# Capteur.net
KiCad netlist of a schematic drawn in Altium Designer
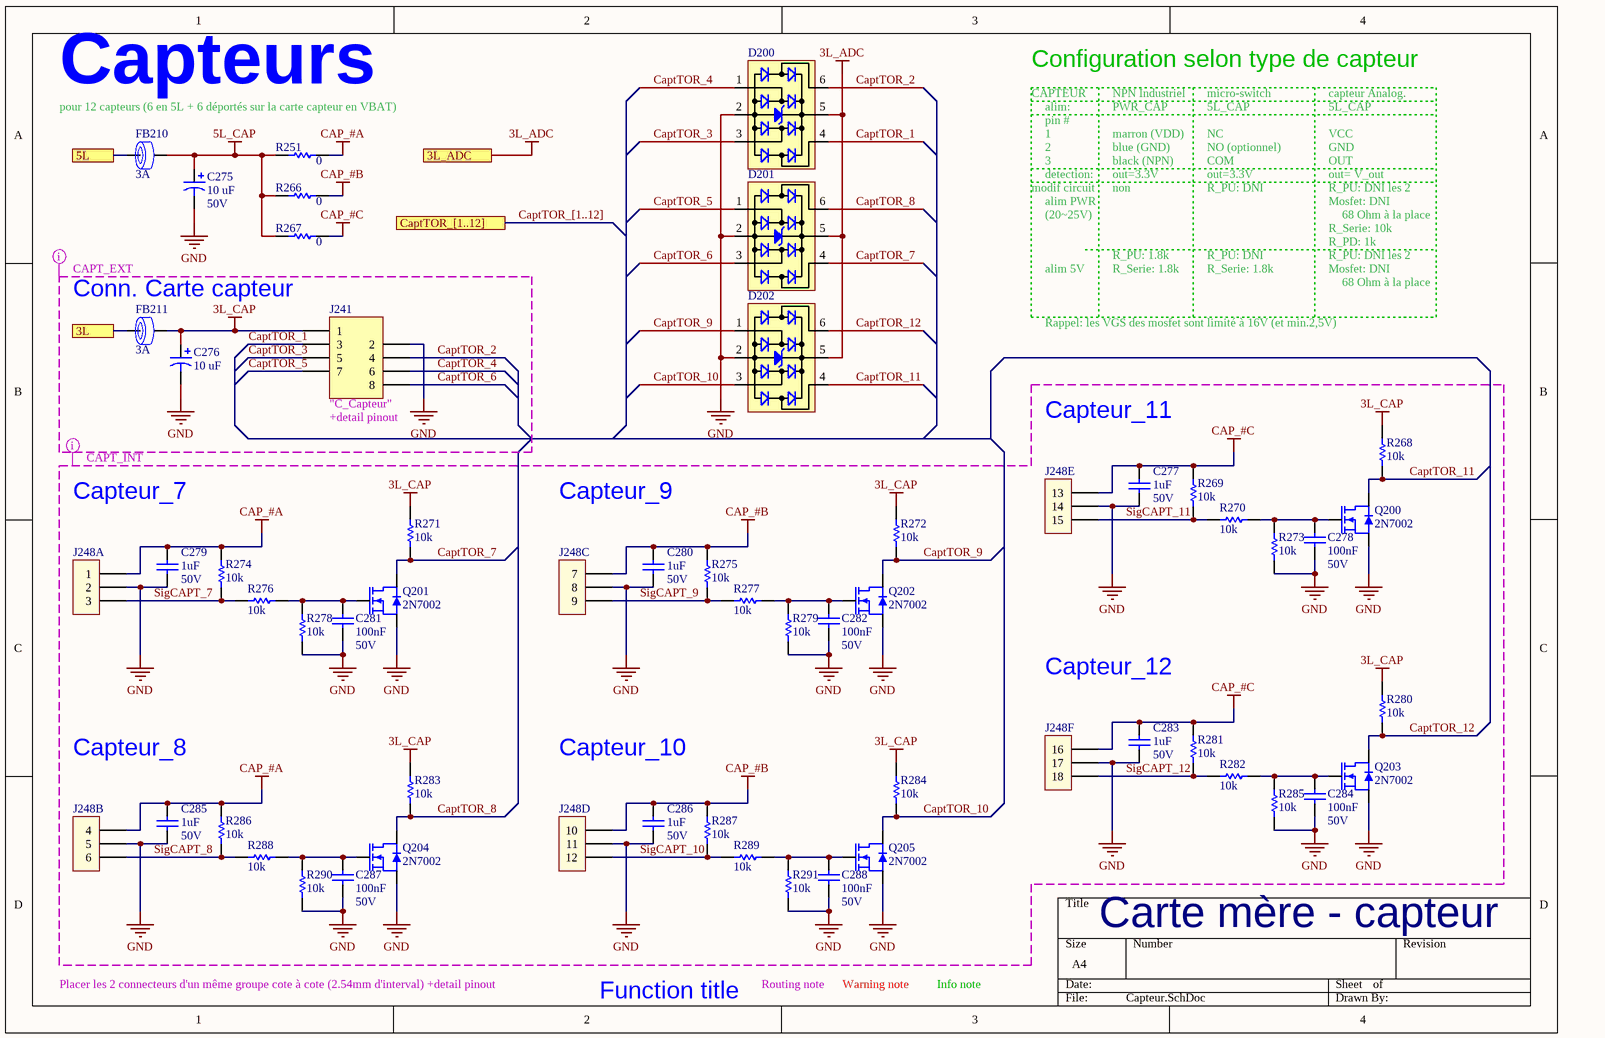
[diagram p0: Capteur.SchDoc]

(export (version "E")
  (design (tool "Eeschema 10.0.6"))
  (components
    (comp (ref "C275")
      (value "10 uF")
      (footprint "WCAP-ATG8_5x11x2x0.5")
      (description "CAP Alu 10 UF 20% 50 V")
      (fields
        (field (name "RATEDVOLTAGE") "50V")
        (field (name "MANUFACTURER") "Wurth Elektronik")
        (field (name "MANUFACTURER PART NUMBER") "860010672009")
      )
      (libsource (lib "Condensateur") (part "WCAP-ATG8, 860010672009"))
    )
    (comp (ref "C276")
      (value "10 uF")
      (footprint "WCAP-ATG8_5x11x2x0.5")
      (description "CAP Alu 10 UF 20% 50 V")
      (fields
        (field (name "MANUFACTURER") "Wurth Elektronik")
        (field (name "MANUFACTURER PART NUMBER") "860010672009")
      )
      (libsource (lib "Condensateur") (part "WCAP-ATG8, 860010672009"))
    )
    (comp (ref "C277")
      (value "1uF")
      (footprint "WCAP-CSGP_0805, 2x1.25x1.25")
      (description "CAP CER 1uF 50V X7R 0805")
      (fields
        (field (name "MANUFACTURER") "Wurth Elektronik")
        (field (name "MANUFACTURER PART NUMBER") "885012207103")
        (field (name "RATEDVOLTAGE") "50V")
      )
      (libsource (lib "Condensateur") (part "WCAP-CSGP, 885012207103"))
    )
    (comp (ref "C278")
      (value "100nF")
      (footprint "WCAP-CSGP_0603, 1.6x0.8x0.8")
      (description "CAP CER 100nF 50V X7R 0603")
      (fields
        (field (name "RATEDVOLTAGE") "50V")
        (field (name "MANUFACTURER") "Wurth Elektronik")
        (field (name "MANUFACTURER PART NUMBER") "885012206095")
      )
      (libsource (lib "Condensateur") (part "WCAP-CSGP, 885012206095"))
    )
    (comp (ref "C279")
      (value "1uF")
      (footprint "WCAP-CSGP_0805, 2x1.25x1.25")
      (description "CAP CER 1uF 50V X7R 0805")
      (fields
        (field (name "MANUFACTURER") "Wurth Elektronik")
        (field (name "MANUFACTURER PART NUMBER") "885012207103")
        (field (name "RATEDVOLTAGE") "50V")
      )
      (libsource (lib "Condensateur") (part "WCAP-CSGP, 885012207103"))
    )
    (comp (ref "C280")
      (value "1uF")
      (footprint "WCAP-CSGP_0805, 2x1.25x1.25")
      (description "CAP CER 1uF 50V X7R 0805")
      (fields
        (field (name "MANUFACTURER") "Wurth Elektronik")
        (field (name "MANUFACTURER PART NUMBER") "885012207103")
        (field (name "RATEDVOLTAGE") "50V")
      )
      (libsource (lib "Condensateur") (part "WCAP-CSGP, 885012207103"))
    )
    (comp (ref "C281")
      (value "100nF")
      (footprint "WCAP-CSGP_0603, 1.6x0.8x0.8")
      (description "CAP CER 100nF 50V X7R 0603")
      (fields
        (field (name "RATEDVOLTAGE") "50V")
        (field (name "MANUFACTURER") "Wurth Elektronik")
        (field (name "MANUFACTURER PART NUMBER") "885012206095")
      )
      (libsource (lib "Condensateur") (part "WCAP-CSGP, 885012206095"))
    )
    (comp (ref "C282")
      (value "100nF")
      (footprint "WCAP-CSGP_0603, 1.6x0.8x0.8")
      (description "CAP CER 100nF 50V X7R 0603")
      (fields
        (field (name "RATEDVOLTAGE") "50V")
        (field (name "MANUFACTURER") "Wurth Elektronik")
        (field (name "MANUFACTURER PART NUMBER") "885012206095")
      )
      (libsource (lib "Condensateur") (part "WCAP-CSGP, 885012206095"))
    )
    (comp (ref "C283")
      (value "1uF")
      (footprint "WCAP-CSGP_0805, 2x1.25x1.25")
      (description "CAP CER 1uF 50V X7R 0805")
      (fields
        (field (name "MANUFACTURER") "Wurth Elektronik")
        (field (name "MANUFACTURER PART NUMBER") "885012207103")
        (field (name "RATEDVOLTAGE") "50V")
      )
      (libsource (lib "Condensateur") (part "WCAP-CSGP, 885012207103"))
    )
    (comp (ref "C284")
      (value "100nF")
      (footprint "WCAP-CSGP_0603, 1.6x0.8x0.8")
      (description "CAP CER 100nF 50V X7R 0603")
      (fields
        (field (name "RATEDVOLTAGE") "50V")
        (field (name "MANUFACTURER") "Wurth Elektronik")
        (field (name "MANUFACTURER PART NUMBER") "885012206095")
      )
      (libsource (lib "Condensateur") (part "WCAP-CSGP, 885012206095"))
    )
    (comp (ref "C285")
      (value "1uF")
      (footprint "WCAP-CSGP_0805, 2x1.25x1.25")
      (description "CAP CER 1uF 50V X7R 0805")
      (fields
        (field (name "MANUFACTURER") "Wurth Elektronik")
        (field (name "MANUFACTURER PART NUMBER") "885012207103")
        (field (name "RATEDVOLTAGE") "50V")
      )
      (libsource (lib "Condensateur") (part "WCAP-CSGP, 885012207103"))
    )
    (comp (ref "C286")
      (value "1uF")
      (footprint "WCAP-CSGP_0805, 2x1.25x1.25")
      (description "CAP CER 1uF 50V X7R 0805")
      (fields
        (field (name "MANUFACTURER") "Wurth Elektronik")
        (field (name "MANUFACTURER PART NUMBER") "885012207103")
        (field (name "RATEDVOLTAGE") "50V")
      )
      (libsource (lib "Condensateur") (part "WCAP-CSGP, 885012207103"))
    )
    (comp (ref "C287")
      (value "100nF")
      (footprint "WCAP-CSGP_0603, 1.6x0.8x0.8")
      (description "CAP CER 100nF 50V X7R 0603")
      (fields
        (field (name "RATEDVOLTAGE") "50V")
        (field (name "MANUFACTURER") "Wurth Elektronik")
        (field (name "MANUFACTURER PART NUMBER") "885012206095")
      )
      (libsource (lib "Condensateur") (part "WCAP-CSGP, 885012206095"))
    )
    (comp (ref "C288")
      (value "100nF")
      (footprint "WCAP-CSGP_0603, 1.6x0.8x0.8")
      (description "CAP CER 100nF 50V X7R 0603")
      (fields
        (field (name "RATEDVOLTAGE") "50V")
        (field (name "MANUFACTURER") "Wurth Elektronik")
        (field (name "MANUFACTURER PART NUMBER") "885012206095")
      )
      (libsource (lib "Condensateur") (part "WCAP-CSGP, 885012206095"))
    )
    (comp (ref "D200")
      (value "824001")
      (footprint "SOT-23-6L")
      (description "WE-TVS TVS Diode 4+1Ch 5V SOT23-6L")
      (fields (field (name "MANUFACTURER") "Wurth Elektronik"))
      (libsource (lib "Diode") (part "824001"))
    )
    (comp (ref "D201")
      (value "824001")
      (footprint "SOT-23-6L")
      (description "WE-TVS TVS Diode 4+1Ch 5V SOT23-6L")
      (fields (field (name "MANUFACTURER") "Wurth Elektronik"))
      (libsource (lib "Diode") (part "824001"))
    )
    (comp (ref "D202")
      (value "824001")
      (footprint "SOT-23-6L")
      (description "WE-TVS TVS Diode 4+1Ch 5V SOT23-6L")
      (fields (field (name "MANUFACTURER") "Wurth Elektronik"))
      (libsource (lib "Diode") (part "824001"))
    )
    (comp (ref "FB210")
      (value "742792023")
      (footprint "WE-CBF_0805_High Current")
      (description "Ferrite Bead 120ohm 0805 3A")
      (fields (field (name "MANUFACTURER") "Wurth Elektronik") (field (name "RATEDCURRENT") "3A"))
      (libsource (lib "Inductance") (part "WE-CBF, 742792023"))
    )
    (comp (ref "FB211")
      (value "742792023")
      (footprint "WE-CBF_0805_High Current")
      (description "Ferrite Bead 120ohm 0805 3A")
      (fields (field (name "MANUFACTURER") "Wurth Elektronik") (field (name "RATEDCURRENT") "3A"))
      (libsource (lib "Inductance") (part "WE-CBF, 742792023"))
    )
    (comp (ref "J241")
      (value "690367280876")
      (footprint "690367280876")
      (description "WR-MM 8p Female SMT Connector with Polarization")
      (fields (field (name "MANUFACTURER") "Wurth Electronics Inc."))
      (libsource (lib "Connecteurs") (part "690367280876"))
    )
    (comp (ref "J248")
      (value "TSW-106-08-F-T-RA")
      (footprint "TSW-106-08-F-T-RA")
      (description "CONN HEADER R/A 3L x 6POS 2.54MM")
      (fields (field (name "MANUFACTURER") "SAMTEC"))
      (libsource (lib "Connecteurs") (part "TSW-106-08-F-T-RA"))
    )
    (comp (ref "Q200")
      (value "2N7002")
      (footprint "SOT-23")
      (description "MOSFET N 60V 115MA SOT23")
      (fields (field (name "MANUFACTURER") "Changjiang Electronics Tech (CJ)"))
      (libsource (lib "Transistors") (part "2N7002"))
    )
    (comp (ref "Q201")
      (value "2N7002")
      (footprint "SOT-23")
      (description "MOSFET N 60V 115MA SOT23")
      (fields (field (name "MANUFACTURER") "Changjiang Electronics Tech (CJ)"))
      (libsource (lib "Transistors") (part "2N7002"))
    )
    (comp (ref "Q202")
      (value "2N7002")
      (footprint "SOT-23")
      (description "MOSFET N 60V 115MA SOT23")
      (fields (field (name "MANUFACTURER") "Changjiang Electronics Tech (CJ)"))
      (libsource (lib "Transistors") (part "2N7002"))
    )
    (comp (ref "Q203")
      (value "2N7002")
      (footprint "SOT-23")
      (description "MOSFET N 60V 115MA SOT23")
      (fields (field (name "MANUFACTURER") "Changjiang Electronics Tech (CJ)"))
      (libsource (lib "Transistors") (part "2N7002"))
    )
    (comp (ref "Q204")
      (value "2N7002")
      (footprint "SOT-23")
      (description "MOSFET N 60V 115MA SOT23")
      (fields (field (name "MANUFACTURER") "Changjiang Electronics Tech (CJ)"))
      (libsource (lib "Transistors") (part "2N7002"))
    )
    (comp (ref "Q205")
      (value "2N7002")
      (footprint "SOT-23")
      (description "MOSFET N 60V 115MA SOT23")
      (fields (field (name "MANUFACTURER") "Changjiang Electronics Tech (CJ)"))
      (libsource (lib "Transistors") (part "2N7002"))
    )
    (comp (ref "R251")
      (value "0")
      (footprint "RESC1608X06N")
      (description "RES SMD 0 OHM 1% 1/10W 0603")
      (fields
        (field (name "MANUFACTURER") "Yageo")
        (field (name "MANUFACTURER PART NUMBER") "RC0603FR-070RL")
      )
      (libsource (lib "Resistance") (part "RC0603FR-070RL"))
    )
    (comp (ref "R266")
      (value "0")
      (footprint "RESC1608X06N")
      (description "RES SMD 0 OHM 1% 1/10W 0603")
      (fields
        (field (name "MANUFACTURER") "Yageo")
        (field (name "MANUFACTURER PART NUMBER") "RC0603FR-070RL")
      )
      (libsource (lib "Resistance") (part "RC0603FR-070RL"))
    )
    (comp (ref "R267")
      (value "0")
      (footprint "RESC1608X06N")
      (description "RES SMD 0 OHM 1% 1/10W 0603")
      (fields
        (field (name "MANUFACTURER") "Yageo")
        (field (name "MANUFACTURER PART NUMBER") "RC0603FR-070RL")
      )
      (libsource (lib "Resistance") (part "RC0603FR-070RL"))
    )
    (comp (ref "R268")
      (value "10k")
      (footprint "RESC1608X06N")
      (description "RES SMD 10K OHM 1% 1/10W 0603")
      (fields
        (field (name "MANUFACTURER") "Yageo")
        (field (name "MANUFACTURER PART NUMBER") "RC0603FR-0710KL")
      )
      (libsource (lib "Resistance") (part "RC0603FR-0710KL"))
    )
    (comp (ref "R269")
      (value "10k")
      (footprint "RESC1608X06N")
      (description "RES SMD 10K OHM 1% 1/10W 0603")
      (fields
        (field (name "MANUFACTURER") "Yageo")
        (field (name "MANUFACTURER PART NUMBER") "RC0603FR-0710KL")
      )
      (libsource (lib "Resistance") (part "RC0603FR-0710KL"))
    )
    (comp (ref "R270")
      (value "10k")
      (footprint "RESC1608X06N")
      (description "RES SMD 10K OHM 1% 1/10W 0603")
      (fields
        (field (name "MANUFACTURER") "Yageo")
        (field (name "MANUFACTURER PART NUMBER") "RC0603FR-0710KL")
      )
      (libsource (lib "Resistance") (part "RC0603FR-0710KL"))
    )
    (comp (ref "R271")
      (value "10k")
      (footprint "RESC1608X06N")
      (description "RES SMD 10K OHM 1% 1/10W 0603")
      (fields
        (field (name "MANUFACTURER") "Yageo")
        (field (name "MANUFACTURER PART NUMBER") "RC0603FR-0710KL")
      )
      (libsource (lib "Resistance") (part "RC0603FR-0710KL"))
    )
    (comp (ref "R272")
      (value "10k")
      (footprint "RESC1608X06N")
      (description "RES SMD 10K OHM 1% 1/10W 0603")
      (fields
        (field (name "MANUFACTURER") "Yageo")
        (field (name "MANUFACTURER PART NUMBER") "RC0603FR-0710KL")
      )
      (libsource (lib "Resistance") (part "RC0603FR-0710KL"))
    )
    (comp (ref "R273")
      (value "10k")
      (footprint "RESC1608X06N")
      (description "RES SMD 10K OHM 1% 1/10W 0603")
      (fields
        (field (name "MANUFACTURER") "Yageo")
        (field (name "MANUFACTURER PART NUMBER") "RC0603FR-0710KL")
      )
      (libsource (lib "Resistance") (part "RC0603FR-0710KL"))
    )
    (comp (ref "R274")
      (value "10k")
      (footprint "RESC1608X06N")
      (description "RES SMD 10K OHM 1% 1/10W 0603")
      (fields
        (field (name "MANUFACTURER") "Yageo")
        (field (name "MANUFACTURER PART NUMBER") "RC0603FR-0710KL")
      )
      (libsource (lib "Resistance") (part "RC0603FR-0710KL"))
    )
    (comp (ref "R275")
      (value "10k")
      (footprint "RESC1608X06N")
      (description "RES SMD 10K OHM 1% 1/10W 0603")
      (fields
        (field (name "MANUFACTURER") "Yageo")
        (field (name "MANUFACTURER PART NUMBER") "RC0603FR-0710KL")
      )
      (libsource (lib "Resistance") (part "RC0603FR-0710KL"))
    )
    (comp (ref "R276")
      (value "10k")
      (footprint "RESC1608X06N")
      (description "RES SMD 10K OHM 1% 1/10W 0603")
      (fields
        (field (name "MANUFACTURER") "Yageo")
        (field (name "MANUFACTURER PART NUMBER") "RC0603FR-0710KL")
      )
      (libsource (lib "Resistance") (part "RC0603FR-0710KL"))
    )
    (comp (ref "R277")
      (value "10k")
      (footprint "RESC1608X06N")
      (description "RES SMD 10K OHM 1% 1/10W 0603")
      (fields
        (field (name "MANUFACTURER") "Yageo")
        (field (name "MANUFACTURER PART NUMBER") "RC0603FR-0710KL")
      )
      (libsource (lib "Resistance") (part "RC0603FR-0710KL"))
    )
    (comp (ref "R278")
      (value "10k")
      (footprint "RESC1608X06N")
      (description "RES SMD 10K OHM 1% 1/10W 0603")
      (fields
        (field (name "MANUFACTURER") "Yageo")
        (field (name "MANUFACTURER PART NUMBER") "RC0603FR-0710KL")
      )
      (libsource (lib "Resistance") (part "RC0603FR-0710KL"))
    )
    (comp (ref "R279")
      (value "10k")
      (footprint "RESC1608X06N")
      (description "RES SMD 10K OHM 1% 1/10W 0603")
      (fields
        (field (name "MANUFACTURER") "Yageo")
        (field (name "MANUFACTURER PART NUMBER") "RC0603FR-0710KL")
      )
      (libsource (lib "Resistance") (part "RC0603FR-0710KL"))
    )
    (comp (ref "R280")
      (value "10k")
      (footprint "RESC1608X06N")
      (description "RES SMD 10K OHM 1% 1/10W 0603")
      (fields
        (field (name "MANUFACTURER") "Yageo")
        (field (name "MANUFACTURER PART NUMBER") "RC0603FR-0710KL")
      )
      (libsource (lib "Resistance") (part "RC0603FR-0710KL"))
    )
    (comp (ref "R281")
      (value "10k")
      (footprint "RESC1608X06N")
      (description "RES SMD 10K OHM 1% 1/10W 0603")
      (fields
        (field (name "MANUFACTURER") "Yageo")
        (field (name "MANUFACTURER PART NUMBER") "RC0603FR-0710KL")
      )
      (libsource (lib "Resistance") (part "RC0603FR-0710KL"))
    )
    (comp (ref "R282")
      (value "10k")
      (footprint "RESC1608X06N")
      (description "RES SMD 10K OHM 1% 1/10W 0603")
      (fields
        (field (name "MANUFACTURER") "Yageo")
        (field (name "MANUFACTURER PART NUMBER") "RC0603FR-0710KL")
      )
      (libsource (lib "Resistance") (part "RC0603FR-0710KL"))
    )
    (comp (ref "R283")
      (value "10k")
      (footprint "RESC1608X06N")
      (description "RES SMD 10K OHM 1% 1/10W 0603")
      (fields
        (field (name "MANUFACTURER") "Yageo")
        (field (name "MANUFACTURER PART NUMBER") "RC0603FR-0710KL")
      )
      (libsource (lib "Resistance") (part "RC0603FR-0710KL"))
    )
    (comp (ref "R284")
      (value "10k")
      (footprint "RESC1608X06N")
      (description "RES SMD 10K OHM 1% 1/10W 0603")
      (fields
        (field (name "MANUFACTURER") "Yageo")
        (field (name "MANUFACTURER PART NUMBER") "RC0603FR-0710KL")
      )
      (libsource (lib "Resistance") (part "RC0603FR-0710KL"))
    )
    (comp (ref "R285")
      (value "10k")
      (footprint "RESC1608X06N")
      (description "RES SMD 10K OHM 1% 1/10W 0603")
      (fields
        (field (name "MANUFACTURER") "Yageo")
        (field (name "MANUFACTURER PART NUMBER") "RC0603FR-0710KL")
      )
      (libsource (lib "Resistance") (part "RC0603FR-0710KL"))
    )
    (comp (ref "R286")
      (value "10k")
      (footprint "RESC1608X06N")
      (description "RES SMD 10K OHM 1% 1/10W 0603")
      (fields
        (field (name "MANUFACTURER") "Yageo")
        (field (name "MANUFACTURER PART NUMBER") "RC0603FR-0710KL")
      )
      (libsource (lib "Resistance") (part "RC0603FR-0710KL"))
    )
    (comp (ref "R287")
      (value "10k")
      (footprint "RESC1608X06N")
      (description "RES SMD 10K OHM 1% 1/10W 0603")
      (fields
        (field (name "MANUFACTURER") "Yageo")
        (field (name "MANUFACTURER PART NUMBER") "RC0603FR-0710KL")
      )
      (libsource (lib "Resistance") (part "RC0603FR-0710KL"))
    )
    (comp (ref "R288")
      (value "10k")
      (footprint "RESC1608X06N")
      (description "RES SMD 10K OHM 1% 1/10W 0603")
      (fields
        (field (name "MANUFACTURER") "Yageo")
        (field (name "MANUFACTURER PART NUMBER") "RC0603FR-0710KL")
      )
      (libsource (lib "Resistance") (part "RC0603FR-0710KL"))
    )
    (comp (ref "R289")
      (value "10k")
      (footprint "RESC1608X06N")
      (description "RES SMD 10K OHM 1% 1/10W 0603")
      (fields
        (field (name "MANUFACTURER") "Yageo")
        (field (name "MANUFACTURER PART NUMBER") "RC0603FR-0710KL")
      )
      (libsource (lib "Resistance") (part "RC0603FR-0710KL"))
    )
    (comp (ref "R290")
      (value "10k")
      (footprint "RESC1608X06N")
      (description "RES SMD 10K OHM 1% 1/10W 0603")
      (fields
        (field (name "MANUFACTURER") "Yageo")
        (field (name "MANUFACTURER PART NUMBER") "RC0603FR-0710KL")
      )
      (libsource (lib "Resistance") (part "RC0603FR-0710KL"))
    )
    (comp (ref "R291")
      (value "10k")
      (footprint "RESC1608X06N")
      (description "RES SMD 10K OHM 1% 1/10W 0603")
      (fields
        (field (name "MANUFACTURER") "Yageo")
        (field (name "MANUFACTURER PART NUMBER") "RC0603FR-0710KL")
      )
      (libsource (lib "Resistance") (part "RC0603FR-0710KL"))
    )
  )
  (nets
    (net (code "1") (name "/3L") (class "Default")
      (node (ref "FB211") (pin "1") (pinfunction "1_1") (pintype "passive"))
    )
    (net (code "2") (name "/5L") (class "Default")
      (node (ref "FB210") (pin "1") (pinfunction "1_1") (pintype "passive"))
    )
    (net (code "3") (name "/CaptTOR_1") (class "Default")
      (node (ref "D200") (pin "4") (pintype "passive"))
      (node (ref "J241") (pin "3") (pinfunction "3_3") (pintype "passive"))
    )
    (net (code "4") (name "/CaptTOR_2") (class "Default")
      (node (ref "D200") (pin "6") (pintype "passive"))
      (node (ref "J241") (pin "4") (pinfunction "4_4") (pintype "passive"))
    )
    (net (code "5") (name "/CaptTOR_3") (class "Default")
      (node (ref "D200") (pin "3") (pintype "passive"))
      (node (ref "J241") (pin "5") (pinfunction "5_5") (pintype "passive"))
    )
    (net (code "6") (name "/CaptTOR_4") (class "Default")
      (node (ref "D200") (pin "1") (pintype "passive"))
      (node (ref "J241") (pin "6") (pinfunction "6_6") (pintype "passive"))
    )
    (net (code "7") (name "/CaptTOR_5") (class "Default")
      (node (ref "D201") (pin "1") (pintype "passive"))
      (node (ref "J241") (pin "7") (pinfunction "7_7") (pintype "passive"))
    )
    (net (code "8") (name "/CaptTOR_6") (class "Default")
      (node (ref "D201") (pin "3") (pintype "passive"))
      (node (ref "J241") (pin "8") (pinfunction "8_8") (pintype "passive"))
    )
    (net (code "9") (name "/CaptTOR_7") (class "Default")
      (node (ref "D201") (pin "4") (pintype "passive"))
      (node (ref "Q201") (pin "3") (pinfunction "D_3") (pintype "passive"))
      (node (ref "R271") (pin "1") (pinfunction "1_1") (pintype "passive"))
    )
    (net (code "10") (name "/CaptTOR_8") (class "Default")
      (node (ref "D201") (pin "6") (pintype "passive"))
      (node (ref "Q204") (pin "3") (pinfunction "D_3") (pintype "passive"))
      (node (ref "R283") (pin "1") (pinfunction "1_1") (pintype "passive"))
    )
    (net (code "11") (name "/CaptTOR_9") (class "Default")
      (node (ref "D202") (pin "1") (pintype "passive"))
      (node (ref "Q202") (pin "3") (pinfunction "D_3") (pintype "passive"))
      (node (ref "R272") (pin "1") (pinfunction "1_1") (pintype "passive"))
    )
    (net (code "12") (name "/CaptTOR_10") (class "Default")
      (node (ref "D202") (pin "3") (pintype "passive"))
      (node (ref "Q205") (pin "3") (pinfunction "D_3") (pintype "passive"))
      (node (ref "R284") (pin "1") (pinfunction "1_1") (pintype "passive"))
    )
    (net (code "13") (name "/CaptTOR_11") (class "Default")
      (node (ref "D202") (pin "4") (pintype "passive"))
      (node (ref "Q200") (pin "3") (pinfunction "D_3") (pintype "passive"))
      (node (ref "R268") (pin "1") (pinfunction "1_1") (pintype "passive"))
    )
    (net (code "14") (name "/CaptTOR_12") (class "Default")
      (node (ref "D202") (pin "6") (pintype "passive"))
      (node (ref "Q203") (pin "3") (pinfunction "D_3") (pintype "passive"))
      (node (ref "R280") (pin "1") (pinfunction "1_1") (pintype "passive"))
    )
    (net (code "16") (name "/SigCAPT_7") (class "Default")
      (node (ref "J248") (pin "3") (pinfunction "3_3") (pintype "passive"))
      (node (ref "R274") (pin "1") (pinfunction "1_1") (pintype "passive"))
      (node (ref "R276") (pin "1") (pinfunction "1_1") (pintype "passive"))
    )
    (net (code "17") (name "/SigCAPT_8") (class "Default")
      (node (ref "J248") (pin "6") (pinfunction "6_6") (pintype "passive"))
      (node (ref "R286") (pin "1") (pinfunction "1_1") (pintype "passive"))
      (node (ref "R288") (pin "1") (pinfunction "1_1") (pintype "passive"))
    )
    (net (code "18") (name "/SigCAPT_9") (class "Default")
      (node (ref "J248") (pin "9") (pinfunction "9_9") (pintype "passive"))
      (node (ref "R275") (pin "1") (pinfunction "1_1") (pintype "passive"))
      (node (ref "R277") (pin "1") (pinfunction "1_1") (pintype "passive"))
    )
    (net (code "19") (name "/SigCAPT_10") (class "Default")
      (node (ref "J248") (pin "12") (pinfunction "12_12") (pintype "passive"))
      (node (ref "R287") (pin "1") (pinfunction "1_1") (pintype "passive"))
      (node (ref "R289") (pin "1") (pinfunction "1_1") (pintype "passive"))
    )
    (net (code "20") (name "/SigCAPT_11") (class "Default")
      (node (ref "J248") (pin "15") (pinfunction "15_15") (pintype "passive"))
      (node (ref "R269") (pin "1") (pinfunction "1_1") (pintype "passive"))
      (node (ref "R270") (pin "1") (pinfunction "1_1") (pintype "passive"))
    )
    (net (code "21") (name "/SigCAPT_12") (class "Default")
      (node (ref "J248") (pin "18") (pinfunction "18_18") (pintype "passive"))
      (node (ref "R281") (pin "1") (pinfunction "1_1") (pintype "passive"))
      (node (ref "R282") (pin "1") (pinfunction "1_1") (pintype "passive"))
    )
    (net (code "22") (name "3L_ADC") (class "Default")
      (node (ref "D200") (pin "5") (pintype "passive"))
      (node (ref "D201") (pin "5") (pintype "passive"))
      (node (ref "D202") (pin "5") (pintype "passive"))
    )
    (net (code "23") (name "3L_CAP") (class "Default")
      (node (ref "C276") (pin "1") (pinfunction "1_1") (pintype "passive"))
      (node (ref "FB211") (pin "2") (pinfunction "2_2") (pintype "passive"))
      (node (ref "J241") (pin "1") (pinfunction "1_1") (pintype "passive"))
      (node (ref "R268") (pin "2") (pinfunction "2_2") (pintype "passive"))
      (node (ref "R271") (pin "2") (pinfunction "2_2") (pintype "passive"))
      (node (ref "R272") (pin "2") (pinfunction "2_2") (pintype "passive"))
      (node (ref "R280") (pin "2") (pinfunction "2_2") (pintype "passive"))
      (node (ref "R283") (pin "2") (pinfunction "2_2") (pintype "passive"))
      (node (ref "R284") (pin "2") (pinfunction "2_2") (pintype "passive"))
    )
    (net (code "24") (name "5L_CAP") (class "Default")
      (node (ref "C275") (pin "1") (pinfunction "1_1") (pintype "passive"))
      (node (ref "FB210") (pin "2") (pinfunction "2_2") (pintype "passive"))
      (node (ref "R251") (pin "1") (pinfunction "1_1") (pintype "passive"))
      (node (ref "R266") (pin "1") (pinfunction "1_1") (pintype "passive"))
      (node (ref "R267") (pin "1") (pinfunction "1_1") (pintype "passive"))
    )
    (net (code "25") (name "CAP_#A") (class "Default")
      (node (ref "C279") (pin "2") (pinfunction "2_2") (pintype "passive"))
      (node (ref "C285") (pin "2") (pinfunction "2_2") (pintype "passive"))
      (node (ref "J248") (pin "1") (pinfunction "1_1") (pintype "passive"))
      (node (ref "J248") (pin "4") (pinfunction "4_4") (pintype "passive"))
      (node (ref "R251") (pin "2") (pinfunction "2_2") (pintype "passive"))
      (node (ref "R274") (pin "2") (pinfunction "2_2") (pintype "passive"))
      (node (ref "R286") (pin "2") (pinfunction "2_2") (pintype "passive"))
    )
    (net (code "26") (name "CAP_#B") (class "Default")
      (node (ref "C280") (pin "2") (pinfunction "2_2") (pintype "passive"))
      (node (ref "C286") (pin "2") (pinfunction "2_2") (pintype "passive"))
      (node (ref "J248") (pin "10") (pinfunction "10_10") (pintype "passive"))
      (node (ref "J248") (pin "7") (pinfunction "7_7") (pintype "passive"))
      (node (ref "R266") (pin "2") (pinfunction "2_2") (pintype "passive"))
      (node (ref "R275") (pin "2") (pinfunction "2_2") (pintype "passive"))
      (node (ref "R287") (pin "2") (pinfunction "2_2") (pintype "passive"))
    )
    (net (code "27") (name "CAP_#C") (class "Default")
      (node (ref "C277") (pin "2") (pinfunction "2_2") (pintype "passive"))
      (node (ref "C283") (pin "2") (pinfunction "2_2") (pintype "passive"))
      (node (ref "J248") (pin "13") (pinfunction "13_13") (pintype "passive"))
      (node (ref "J248") (pin "16") (pinfunction "16_16") (pintype "passive"))
      (node (ref "R267") (pin "2") (pinfunction "2_2") (pintype "passive"))
      (node (ref "R269") (pin "2") (pinfunction "2_2") (pintype "passive"))
      (node (ref "R281") (pin "2") (pinfunction "2_2") (pintype "passive"))
    )
    (net (code "28") (name "GND") (class "Default")
      (node (ref "C275") (pin "2") (pinfunction "2_2") (pintype "passive"))
      (node (ref "C276") (pin "2") (pinfunction "2_2") (pintype "passive"))
      (node (ref "C277") (pin "1") (pinfunction "1_1") (pintype "passive"))
      (node (ref "C278") (pin "2") (pinfunction "2_2") (pintype "passive"))
      (node (ref "C279") (pin "1") (pinfunction "1_1") (pintype "passive"))
      (node (ref "C280") (pin "1") (pinfunction "1_1") (pintype "passive"))
      (node (ref "C281") (pin "2") (pinfunction "2_2") (pintype "passive"))
      (node (ref "C282") (pin "2") (pinfunction "2_2") (pintype "passive"))
      (node (ref "C283") (pin "1") (pinfunction "1_1") (pintype "passive"))
      (node (ref "C284") (pin "2") (pinfunction "2_2") (pintype "passive"))
      (node (ref "C285") (pin "1") (pinfunction "1_1") (pintype "passive"))
      (node (ref "C286") (pin "1") (pinfunction "1_1") (pintype "passive"))
      (node (ref "C287") (pin "2") (pinfunction "2_2") (pintype "passive"))
      (node (ref "C288") (pin "2") (pinfunction "2_2") (pintype "passive"))
      (node (ref "D200") (pin "2") (pintype "passive"))
      (node (ref "D201") (pin "2") (pintype "passive"))
      (node (ref "D202") (pin "2") (pintype "passive"))
      (node (ref "J241") (pin "2") (pinfunction "2_2") (pintype "passive"))
      (node (ref "J248") (pin "11") (pinfunction "11_11") (pintype "passive"))
      (node (ref "J248") (pin "14") (pinfunction "14_14") (pintype "passive"))
      (node (ref "J248") (pin "17") (pinfunction "17_17") (pintype "passive"))
      (node (ref "J248") (pin "2") (pinfunction "2_2") (pintype "passive"))
      (node (ref "J248") (pin "5") (pinfunction "5_5") (pintype "passive"))
      (node (ref "J248") (pin "8") (pinfunction "8_8") (pintype "passive"))
      (node (ref "Q200") (pin "2") (pinfunction "S_2") (pintype "passive"))
      (node (ref "Q201") (pin "2") (pinfunction "S_2") (pintype "passive"))
      (node (ref "Q202") (pin "2") (pinfunction "S_2") (pintype "passive"))
      (node (ref "Q203") (pin "2") (pinfunction "S_2") (pintype "passive"))
      (node (ref "Q204") (pin "2") (pinfunction "S_2") (pintype "passive"))
      (node (ref "Q205") (pin "2") (pinfunction "S_2") (pintype "passive"))
      (node (ref "R273") (pin "1") (pinfunction "1_1") (pintype "passive"))
      (node (ref "R278") (pin "1") (pinfunction "1_1") (pintype "passive"))
      (node (ref "R279") (pin "1") (pinfunction "1_1") (pintype "passive"))
      (node (ref "R285") (pin "1") (pinfunction "1_1") (pintype "passive"))
      (node (ref "R290") (pin "1") (pinfunction "1_1") (pintype "passive"))
      (node (ref "R291") (pin "1") (pinfunction "1_1") (pintype "passive"))
    )
    (net (code "29") (name "Net-(Q200-G)") (class "Default")
      (node (ref "C278") (pin "1") (pinfunction "1_1") (pintype "passive"))
      (node (ref "Q200") (pin "1") (pinfunction "G_1") (pintype "passive"))
      (node (ref "R270") (pin "2") (pinfunction "2_2") (pintype "passive"))
      (node (ref "R273") (pin "2") (pinfunction "2_2") (pintype "passive"))
    )
    (net (code "30") (name "Net-(Q201-G)") (class "Default")
      (node (ref "C281") (pin "1") (pinfunction "1_1") (pintype "passive"))
      (node (ref "Q201") (pin "1") (pinfunction "G_1") (pintype "passive"))
      (node (ref "R276") (pin "2") (pinfunction "2_2") (pintype "passive"))
      (node (ref "R278") (pin "2") (pinfunction "2_2") (pintype "passive"))
    )
    (net (code "31") (name "Net-(Q202-G)") (class "Default")
      (node (ref "C282") (pin "1") (pinfunction "1_1") (pintype "passive"))
      (node (ref "Q202") (pin "1") (pinfunction "G_1") (pintype "passive"))
      (node (ref "R277") (pin "2") (pinfunction "2_2") (pintype "passive"))
      (node (ref "R279") (pin "2") (pinfunction "2_2") (pintype "passive"))
    )
    (net (code "32") (name "Net-(Q203-G)") (class "Default")
      (node (ref "C284") (pin "1") (pinfunction "1_1") (pintype "passive"))
      (node (ref "Q203") (pin "1") (pinfunction "G_1") (pintype "passive"))
      (node (ref "R282") (pin "2") (pinfunction "2_2") (pintype "passive"))
      (node (ref "R285") (pin "2") (pinfunction "2_2") (pintype "passive"))
    )
    (net (code "33") (name "Net-(Q204-G)") (class "Default")
      (node (ref "C287") (pin "1") (pinfunction "1_1") (pintype "passive"))
      (node (ref "Q204") (pin "1") (pinfunction "G_1") (pintype "passive"))
      (node (ref "R288") (pin "2") (pinfunction "2_2") (pintype "passive"))
      (node (ref "R290") (pin "2") (pinfunction "2_2") (pintype "passive"))
    )
    (net (code "34") (name "Net-(Q205-G)") (class "Default")
      (node (ref "C288") (pin "1") (pinfunction "1_1") (pintype "passive"))
      (node (ref "Q205") (pin "1") (pinfunction "G_1") (pintype "passive"))
      (node (ref "R289") (pin "2") (pinfunction "2_2") (pintype "passive"))
      (node (ref "R291") (pin "2") (pinfunction "2_2") (pintype "passive"))
    )
  )
)
